# pwrthougts.net
KiCad netlist of a schematic drawn in EAGLE
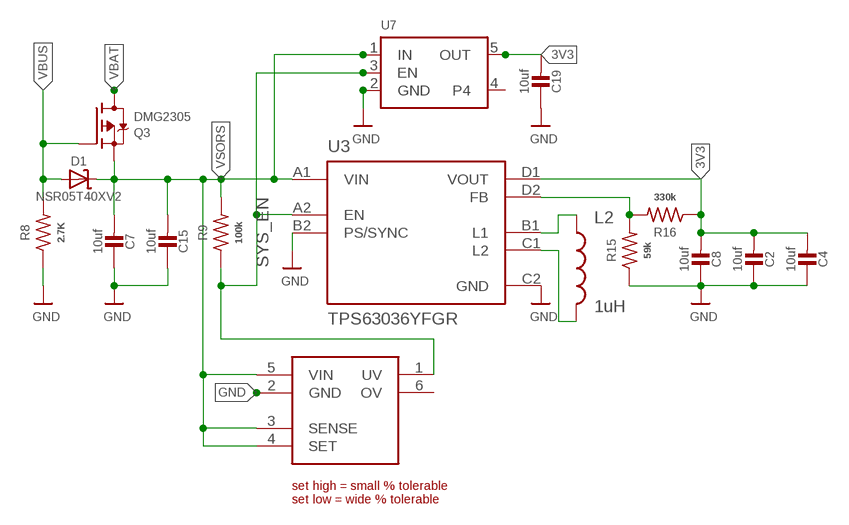
[diagram p0: schematic, sheet 1]

(export (version "E")
  (design (tool "Eeschema 10.0.6"))
  (components
    (comp (ref "C2")
      (value "10uf")
      (footprint "eagle-import:MICROBUILDER__0402_NODIMS")
      (libsource (lib "eagle-import") (part "C-US__0402_NOMASK"))
    )
    (comp (ref "C4")
      (value "10uf")
      (footprint "eagle-import:MICROBUILDER__0402_NODIMS")
      (libsource (lib "eagle-import") (part "C-US__0402_NOMASK"))
    )
    (comp (ref "C7")
      (value "10uf")
      (footprint "eagle-import:MICROBUILDER__0402_NODIMS")
      (libsource (lib "eagle-import") (part "C-US__0402_NOMASK"))
    )
    (comp (ref "C8")
      (value "10uf")
      (footprint "eagle-import:MICROBUILDER__0402_NODIMS")
      (libsource (lib "eagle-import") (part "C-US__0402_NOMASK"))
    )
    (comp (ref "C15")
      (value "10uf")
      (footprint "eagle-import:MICROBUILDER__0402_NODIMS")
      (libsource (lib "eagle-import") (part "C-US__0402_NOMASK"))
    )
    (comp (ref "C19")
      (value "10uf")
      (footprint "eagle-import:MICROBUILDER__0402_NODIMS")
      (libsource (lib "eagle-import") (part "C-US__0402_NOMASK"))
    )
    (comp (ref "D1")
      (value "NSR05T40XV2")
      (footprint "eagle-import:SOD-523")
      (libsource (lib "eagle-import") (part "DIODE-SCHOTTKYSOD-523"))
    )
    (comp (ref "L2")
      (value "1uH")
      (footprint "eagle-import:NONSTANDARD_INDUCTOR_5")
      (libsource (lib "eagle-import") (part "INDUCTOR_1UHMEDIUM_CURRENT"))
    )
    (comp (ref "Q3")
      (value "DMG2305")
      (footprint "eagle-import:SOT23-R")
      (libsource (lib "eagle-import") (part "MOSFET-P"))
    )
    (comp (ref "R8")
      (value "2.7K")
      (footprint "eagle-import:TG_0402")
      (libsource (lib "eagle-import") (part "R_TG_0402"))
    )
    (comp (ref "R9")
      (value "100k")
      (footprint "eagle-import:TG_0402")
      (libsource (lib "eagle-import") (part "R_TG_0402"))
    )
    (comp (ref "R15")
      (value "59k")
      (footprint "eagle-import:TG_0402")
      (libsource (lib "eagle-import") (part "R_TG_0402"))
    )
    (comp (ref "R16")
      (value "330k")
      (footprint "eagle-import:TG_0402")
      (libsource (lib "eagle-import") (part "R_TG_0402"))
    )
    (comp (ref "U3")
      (value "TPS63036YFGR")
      (footprint "eagle-import:BGA8N40P4X2_181X107X62N")
      (fields (field (name "MF") "Texas Instruments"))
      (libsource (lib "eagle-import") (part "TPS63036YFGR"))
    )
    (comp (ref "U7")
      (value "VREG_STD_MIN_SOT23-5")
      (footprint "eagle-import:SOT23-5")
      (libsource (lib "eagle-import") (part "VREG_STD_MIN_SOT23-5"))
    )
    (comp (ref "U8")
      (value "UNDERVOLT-TPS3702CX3")
      (footprint "eagle-import:SOT95P280X110-6N")
      (libsource (lib "eagle-import") (part "UNDERVOLT-TPS3702CX3"))
    )
  )
  (nets
    (net (code "1") (name "/SYS_EN") (class "Default")
      (node (ref "R9") (pin "1") (pinfunction "1_1") (pintype "passive"))
      (node (ref "U3") (pin "A2") (pinfunction "EN_A2") (pintype "input"))
      (node (ref "U7") (pin "3") (pinfunction "EN_3") (pintype "input"))
      (node (ref "U8") (pin "1") (pinfunction "UV_1") (pintype "bidirectional"))
    )
    (net (code "2") (name "3V3") (class "Default")
      (node (ref "C19") (pin "2") (pinfunction "2_2") (pintype "passive"))
      (node (ref "C2") (pin "2") (pinfunction "2_2") (pintype "passive"))
      (node (ref "C4") (pin "2") (pinfunction "2_2") (pintype "passive"))
      (node (ref "C8") (pin "2") (pinfunction "2_2") (pintype "passive"))
      (node (ref "R16") (pin "1") (pinfunction "1_1") (pintype "passive"))
      (node (ref "U3") (pin "D1") (pinfunction "VOUT_D1") (pintype "output"))
      (node (ref "U7") (pin "5") (pinfunction "OUT_5") (pintype "power_in"))
    )
    (net (code "3") (name "GND") (class "Default")
      (node (ref "C15") (pin "1") (pinfunction "1_1") (pintype "passive"))
      (node (ref "C19") (pin "1") (pinfunction "1_1") (pintype "passive"))
      (node (ref "C2") (pin "1") (pinfunction "1_1") (pintype "passive"))
      (node (ref "C4") (pin "1") (pinfunction "1_1") (pintype "passive"))
      (node (ref "C7") (pin "1") (pinfunction "1_1") (pintype "passive"))
      (node (ref "C8") (pin "1") (pinfunction "1_1") (pintype "passive"))
      (node (ref "R15") (pin "1") (pinfunction "1_1") (pintype "passive"))
      (node (ref "R8") (pin "1") (pinfunction "1_1") (pintype "passive"))
      (node (ref "U3") (pin "B2") (pinfunction "PS/SYNC_B2") (pintype "input"))
      (node (ref "U3") (pin "C2") (pinfunction "GND_C2") (pintype "power_in"))
      (node (ref "U7") (pin "2") (pinfunction "GND_2") (pintype "power_in"))
      (node (ref "U8") (pin "2") (pinfunction "GND_2") (pintype "bidirectional"))
    )
    (net (code "4") (name "Net-(U3-FB)") (class "Default")
      (node (ref "R15") (pin "2") (pinfunction "2_2") (pintype "passive"))
      (node (ref "R16") (pin "2") (pinfunction "2_2") (pintype "passive"))
      (node (ref "U3") (pin "D2") (pinfunction "FB_D2") (pintype "input"))
    )
    (net (code "5") (name "Net-(U3-L1)") (class "Default")
      (node (ref "L2") (pin "1") (pinfunction "1_1") (pintype "passive"))
      (node (ref "U3") (pin "B1") (pinfunction "L1_B1") (pintype "passive"))
    )
    (net (code "6") (name "Net-(U3-L2)") (class "Default")
      (node (ref "L2") (pin "2") (pinfunction "2_2") (pintype "passive"))
      (node (ref "U3") (pin "C1") (pinfunction "L2_C1") (pintype "passive"))
    )
    (net (code "7") (name "VBAT") (class "Default")
      (node (ref "Q3") (pin "3") (pinfunction "D_3") (pintype "passive"))
    )
    (net (code "8") (name "VBUS") (class "Default")
      (node (ref "D1") (pin "A") (pinfunction "A_A") (pintype "passive"))
      (node (ref "Q3") (pin "1") (pinfunction "G_1") (pintype "passive"))
      (node (ref "R8") (pin "2") (pinfunction "2_2") (pintype "passive"))
    )
    (net (code "9") (name "VSORS") (class "Default")
      (node (ref "C15") (pin "2") (pinfunction "2_2") (pintype "passive"))
      (node (ref "C7") (pin "2") (pinfunction "2_2") (pintype "passive"))
      (node (ref "D1") (pin "K") (pinfunction "C_K") (pintype "passive"))
      (node (ref "Q3") (pin "2") (pinfunction "S_2") (pintype "passive"))
      (node (ref "R9") (pin "2") (pinfunction "2_2") (pintype "passive"))
      (node (ref "U3") (pin "A1") (pinfunction "VIN_A1") (pintype "input"))
      (node (ref "U7") (pin "1") (pinfunction "IN_1") (pintype "power_in"))
      (node (ref "U8") (pin "3") (pinfunction "SENSE_3") (pintype "bidirectional"))
      (node (ref "U8") (pin "4") (pinfunction "SET_4") (pintype "bidirectional"))
      (node (ref "U8") (pin "5") (pinfunction "VIN_5") (pintype "bidirectional"))
    )
    (net (code "10") (name "unconnected-(U7-P4-Pad4)") (class "Default")
      (node (ref "U7") (pin "4") (pinfunction "P4_4") (pintype "bidirectional"))
    )
    (net (code "11") (name "unconnected-(U8-OV-Pad6)") (class "Default")
      (node (ref "U8") (pin "6") (pinfunction "OV_6") (pintype "bidirectional"))
    )
  )
)
